# Rephone_core_2G-AtmelSAMD21_v1_0.net
KiCad netlist of a schematic drawn in EAGLE
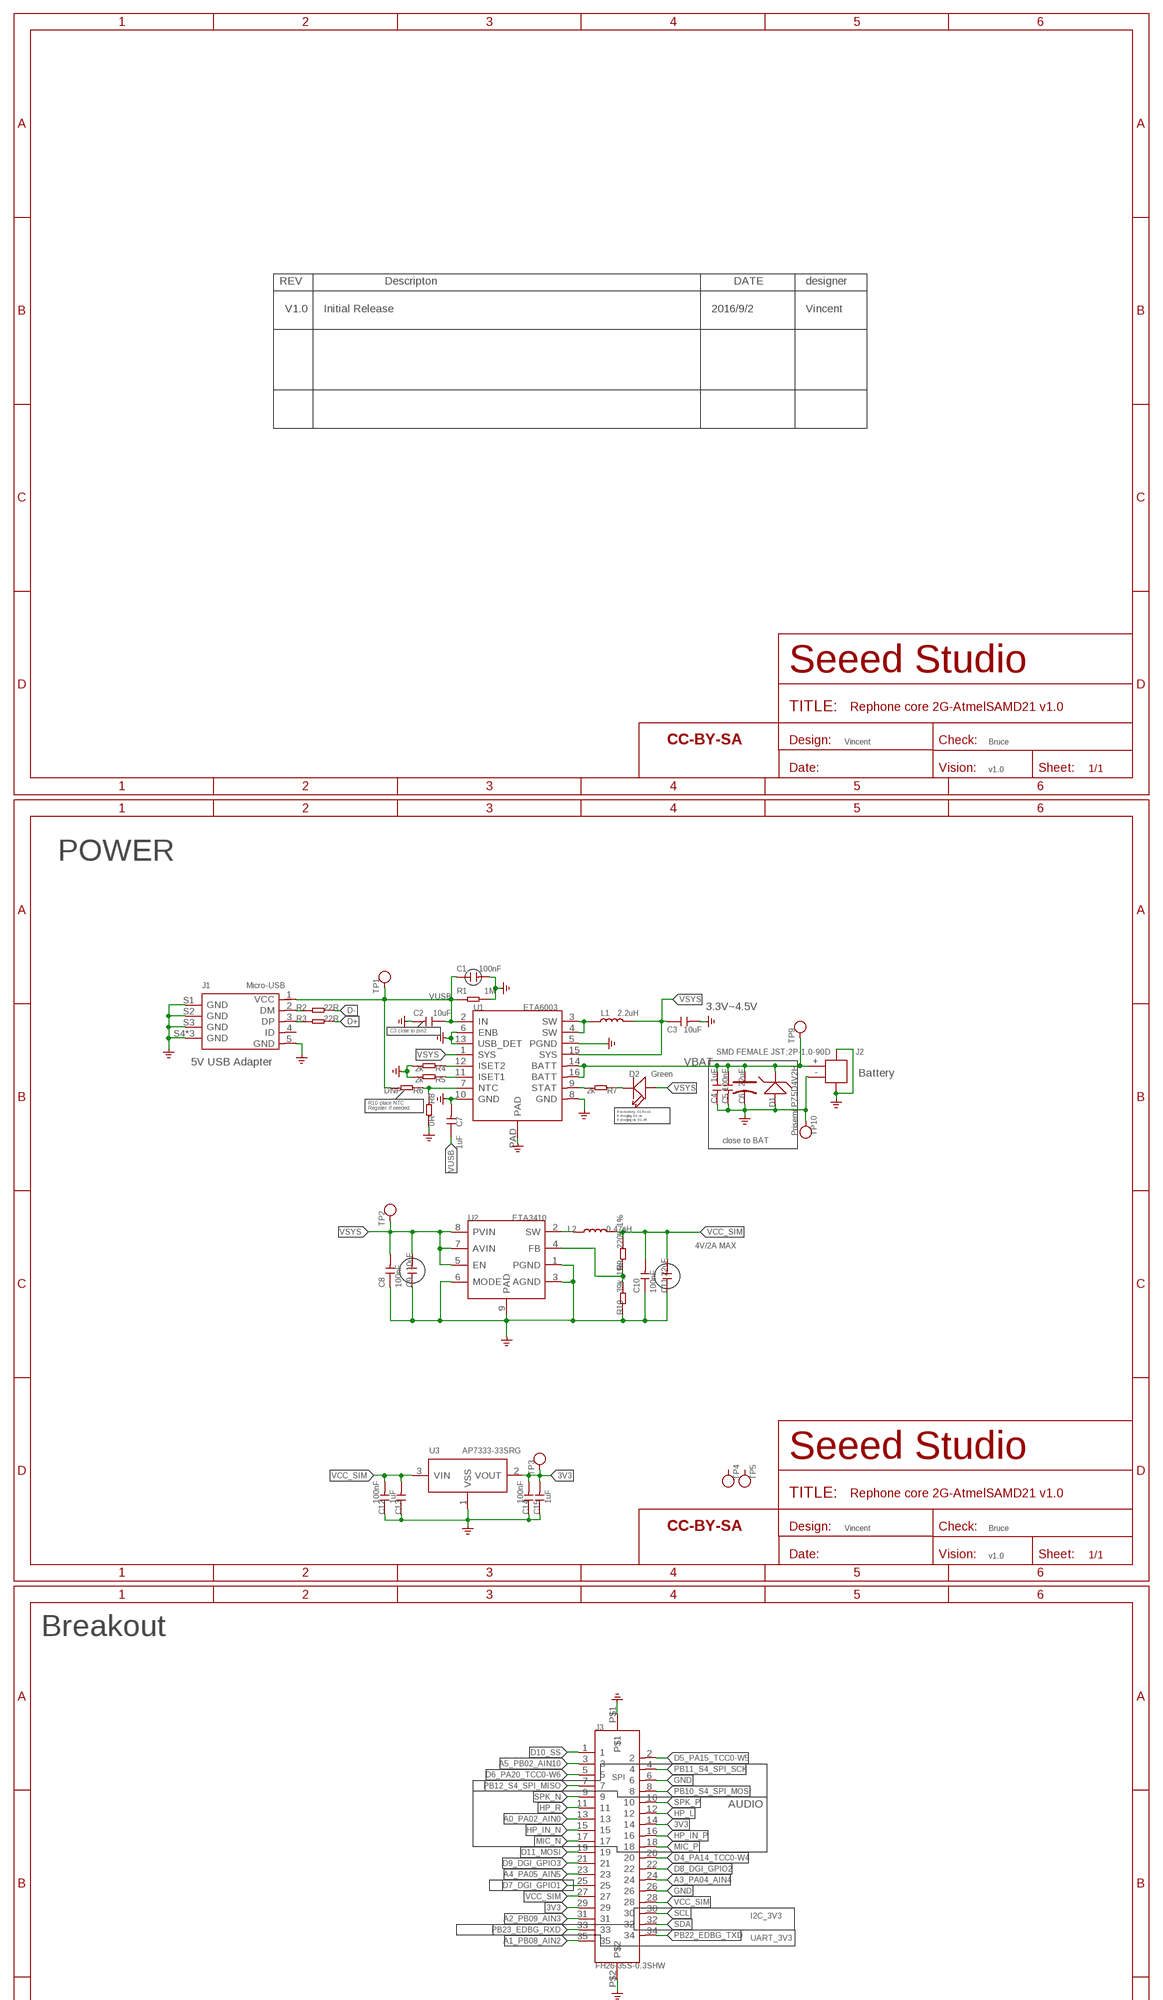
[diagram p0: schematic, sheet 1, part 1 of 2]
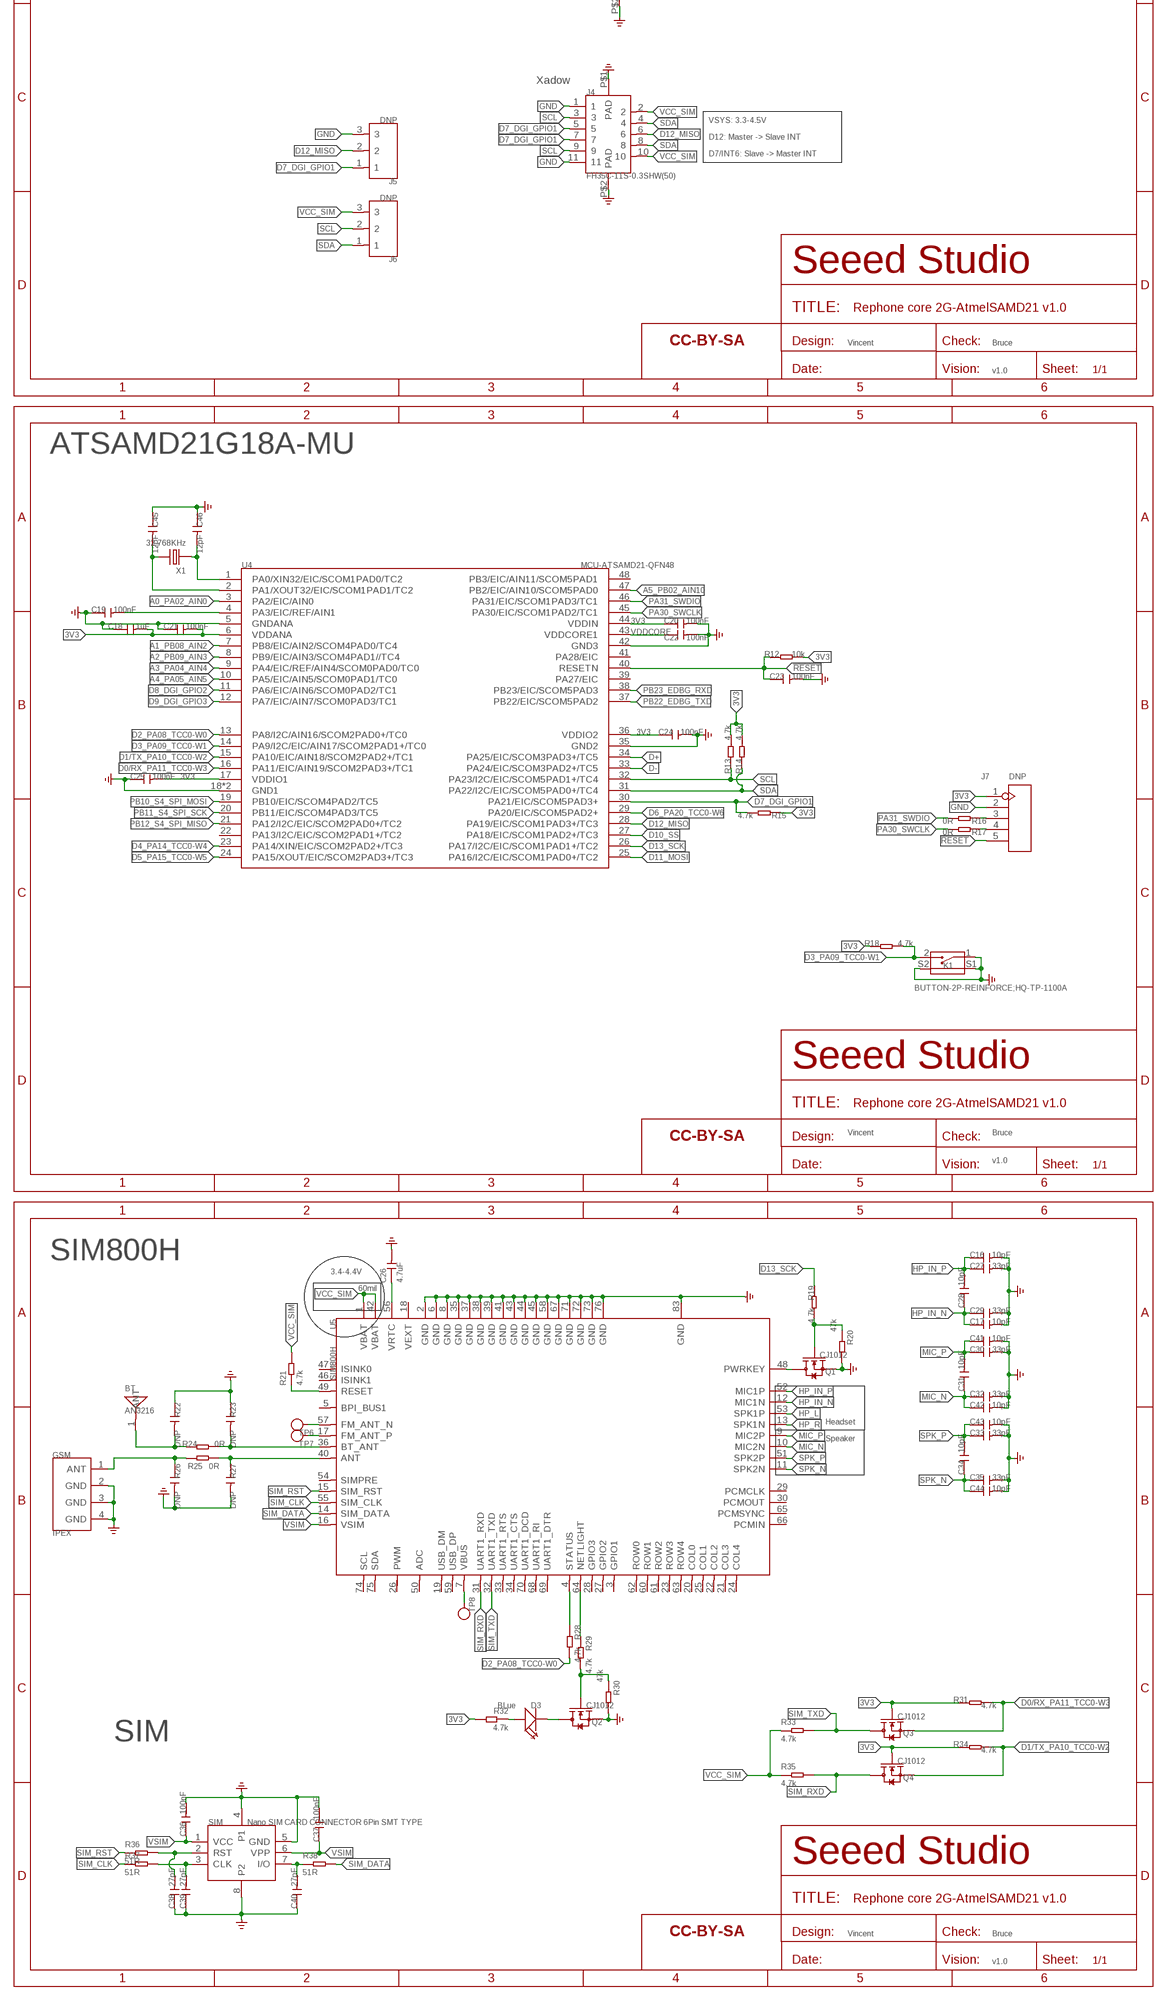
[diagram p1: schematic, sheet 1, part 2 of 2]

(export (version "E")
  (design (tool "Eeschema 10.0.6"))
  (components
    (comp (ref "BT")
      (value "AN3216")
      (footprint "eagle-import:ANT-SMD2P-3.2X1.6X1.04MM")
      (libsource (lib "eagle-import") (part "ANTENNA-AN3216"))
    )
    (comp (ref "C1")
      (value "100nF")
      (footprint "eagle-import:C0201")
      (libsource (lib "eagle-import") (part "CAP-0201"))
    )
    (comp (ref "C2")
      (value "10uF")
      (footprint "eagle-import:C0603")
      (libsource (lib "eagle-import") (part "C-0603"))
    )
    (comp (ref "C3")
      (value "10uF")
      (footprint "eagle-import:C0603")
      (libsource (lib "eagle-import") (part "C-0603"))
    )
    (comp (ref "C4")
      (value "1uF")
      (footprint "eagle-import:C0402")
      (libsource (lib "eagle-import") (part "C-0402"))
    )
    (comp (ref "C5")
      (value "100nF")
      (footprint "eagle-import:C0201")
      (libsource (lib "eagle-import") (part "CAP-0201"))
    )
    (comp (ref "C6")
      (value "22uF")
      (footprint "eagle-import:AVX-A")
      (libsource (lib "eagle-import") (part "CAP-POLAR-AVX-A"))
    )
    (comp (ref "C7")
      (value "1uF")
      (footprint "eagle-import:C0402")
      (libsource (lib "eagle-import") (part "C-0402"))
    )
    (comp (ref "C8")
      (value "100nF")
      (footprint "eagle-import:C0201")
      (libsource (lib "eagle-import") (part "CAP-0201"))
    )
    (comp (ref "C9")
      (value "10uF")
      (footprint "eagle-import:C0603")
      (libsource (lib "eagle-import") (part "C-0603"))
    )
    (comp (ref "C10")
      (value "100nF")
      (footprint "eagle-import:C0201")
      (libsource (lib "eagle-import") (part "CAP-0201"))
    )
    (comp (ref "C11")
      (value "22uF")
      (footprint "eagle-import:C0603")
      (libsource (lib "eagle-import") (part "C-0603"))
    )
    (comp (ref "C12")
      (value "100nF")
      (footprint "eagle-import:C0201")
      (libsource (lib "eagle-import") (part "CAP-0201"))
    )
    (comp (ref "C13")
      (value "1uF")
      (footprint "eagle-import:C0402")
      (libsource (lib "eagle-import") (part "C-0402"))
    )
    (comp (ref "C14")
      (value "100nF")
      (footprint "eagle-import:C0201")
      (libsource (lib "eagle-import") (part "CAP-0201"))
    )
    (comp (ref "C15")
      (value "1uF")
      (footprint "eagle-import:C0402")
      (libsource (lib "eagle-import") (part "C-0402"))
    )
    (comp (ref "C16")
      (value "10pF")
      (footprint "eagle-import:C0201")
      (libsource (lib "eagle-import") (part "CAP-0201"))
    )
    (comp (ref "C17")
      (value "10pF")
      (footprint "eagle-import:C0201")
      (libsource (lib "eagle-import") (part "CAP-0201"))
    )
    (comp (ref "C18")
      (value "1uF")
      (footprint "eagle-import:C0402")
      (libsource (lib "eagle-import") (part "C-0402"))
    )
    (comp (ref "C19")
      (value "100nF")
      (footprint "eagle-import:C0201")
      (libsource (lib "eagle-import") (part "CAP-0201"))
    )
    (comp (ref "C20")
      (value "100nF")
      (footprint "eagle-import:C0201")
      (libsource (lib "eagle-import") (part "CAP-0201"))
    )
    (comp (ref "C21")
      (value "100nF")
      (footprint "eagle-import:C0201")
      (libsource (lib "eagle-import") (part "CAP-0201"))
    )
    (comp (ref "C22")
      (value "100nF")
      (footprint "eagle-import:C0201")
      (libsource (lib "eagle-import") (part "CAP-0201"))
    )
    (comp (ref "C23")
      (value "100nF")
      (footprint "eagle-import:C0201")
      (libsource (lib "eagle-import") (part "CAP-0201"))
    )
    (comp (ref "C24")
      (value "100nF")
      (footprint "eagle-import:C0201")
      (libsource (lib "eagle-import") (part "CAP-0201"))
    )
    (comp (ref "C25")
      (value "100nF")
      (footprint "eagle-import:C0201")
      (libsource (lib "eagle-import") (part "CAP-0201"))
    )
    (comp (ref "C26")
      (value "4.7uF")
      (footprint "eagle-import:C0603")
      (libsource (lib "eagle-import") (part "CAP-0603"))
    )
    (comp (ref "C27")
      (value "33pF")
      (footprint "eagle-import:C0201")
      (libsource (lib "eagle-import") (part "CAP-0201"))
    )
    (comp (ref "C28")
      (value "10pF")
      (footprint "eagle-import:C0201")
      (libsource (lib "eagle-import") (part "CAP-0201"))
    )
    (comp (ref "C29")
      (value "33pF")
      (footprint "eagle-import:C0201")
      (libsource (lib "eagle-import") (part "CAP-0201"))
    )
    (comp (ref "C30")
      (value "33pF")
      (footprint "eagle-import:C0201")
      (libsource (lib "eagle-import") (part "CAP-0201"))
    )
    (comp (ref "C31")
      (value "10pF")
      (footprint "eagle-import:C0201")
      (libsource (lib "eagle-import") (part "CAP-0201"))
    )
    (comp (ref "C32")
      (value "33pF")
      (footprint "eagle-import:C0201")
      (libsource (lib "eagle-import") (part "CAP-0201"))
    )
    (comp (ref "C33")
      (value "33pF")
      (footprint "eagle-import:C0201")
      (libsource (lib "eagle-import") (part "CAP-0201"))
    )
    (comp (ref "C34")
      (value "10pF")
      (footprint "eagle-import:C0201")
      (libsource (lib "eagle-import") (part "CAP-0201"))
    )
    (comp (ref "C35")
      (value "33pF")
      (footprint "eagle-import:C0201")
      (libsource (lib "eagle-import") (part "CAP-0201"))
    )
    (comp (ref "C36")
      (value "100nF")
      (footprint "eagle-import:C0201")
      (libsource (lib "eagle-import") (part "CAP-0201"))
    )
    (comp (ref "C37")
      (value "100nF")
      (footprint "eagle-import:C0201")
      (libsource (lib "eagle-import") (part "CAP-0201"))
    )
    (comp (ref "C38")
      (value "27pF")
      (footprint "eagle-import:C0201")
      (libsource (lib "eagle-import") (part "CAP-0201"))
    )
    (comp (ref "C39")
      (value "27pF")
      (footprint "eagle-import:C0201")
      (libsource (lib "eagle-import") (part "CAP-0201"))
    )
    (comp (ref "C40")
      (value "27pF")
      (footprint "eagle-import:C0201")
      (libsource (lib "eagle-import") (part "CAP-0201"))
    )
    (comp (ref "C41")
      (value "10pF")
      (footprint "eagle-import:C0201")
      (libsource (lib "eagle-import") (part "CAP-0201"))
    )
    (comp (ref "C42")
      (value "10pF")
      (footprint "eagle-import:C0201")
      (libsource (lib "eagle-import") (part "CAP-0201"))
    )
    (comp (ref "C43")
      (value "10pF")
      (footprint "eagle-import:C0201")
      (libsource (lib "eagle-import") (part "CAP-0201"))
    )
    (comp (ref "C44")
      (value "10pF")
      (footprint "eagle-import:C0201")
      (libsource (lib "eagle-import") (part "CAP-0201"))
    )
    (comp (ref "C45")
      (value "12pF")
      (footprint "eagle-import:C0201")
      (libsource (lib "eagle-import") (part "CAP-0201"))
    )
    (comp (ref "C46")
      (value "12pF")
      (footprint "eagle-import:C0201")
      (libsource (lib "eagle-import") (part "CAP-0201"))
    )
    (comp (ref "D1")
      (value "Prisemi;PZ5D4V2H")
      (footprint "eagle-import:SOD-523")
      (libsource (lib "eagle-import") (part "D-ZENER-2P'BZX584CX'"))
    )
    (comp (ref "D2")
      (value "Green")
      (footprint "eagle-import:LED-0402")
      (libsource (lib "eagle-import") (part "LED-0402"))
    )
    (comp (ref "D3")
      (value "BLue")
      (footprint "eagle-import:LED-0402")
      (libsource (lib "eagle-import") (part "LED-0402"))
    )
    (comp (ref "FR1")
      (value "SEEEDSTUDIO-OPEN-SCH-FRAME")
      (footprint "eagle-import:SEEEDSTUDIO-PCB-FRAME")
      (libsource (lib "eagle-import") (part "SEEEDSTUDIO-OPEN-SCH-FRAME"))
    )
    (comp (ref "FR2")
      (value "SEEEDSTUDIO-OPEN-SCH-FRAME")
      (footprint "eagle-import:SEEEDSTUDIO-PCB-FRAME")
      (libsource (lib "eagle-import") (part "SEEEDSTUDIO-OPEN-SCH-FRAME"))
    )
    (comp (ref "FR3")
      (value "SEEEDSTUDIO-OPEN-SCH-FRAME")
      (footprint "eagle-import:SEEEDSTUDIO-PCB-FRAME")
      (libsource (lib "eagle-import") (part "SEEEDSTUDIO-OPEN-SCH-FRAME"))
    )
    (comp (ref "FR4")
      (value "SEEEDSTUDIO-OPEN-SCH-FRAME")
      (footprint "eagle-import:SEEEDSTUDIO-PCB-FRAME")
      (libsource (lib "eagle-import") (part "SEEEDSTUDIO-OPEN-SCH-FRAME"))
    )
    (comp (ref "FR5")
      (value "SEEEDSTUDIO-OPEN-SCH-FRAME")
      (footprint "eagle-import:SEEEDSTUDIO-PCB-FRAME")
      (libsource (lib "eagle-import") (part "SEEEDSTUDIO-OPEN-SCH-FRAME"))
    )
    (comp (ref "GSM")
      (value "IPEX")
      (footprint "eagle-import:ANT-IPEX4-1.7X1.7MM")
      (libsource (lib "eagle-import") (part "ANT_IPEX"))
    )
    (comp (ref "J1")
      (value "Micro-USB")
      (footprint "eagle-import:MICRO-USB5+4P-SMD-0.65-B")
      (libsource (lib "eagle-import") (part "MICRO-USB5+4P5+4P"))
    )
    (comp (ref "J2")
      (value "SMD FEMALE JST;2P-1.0-90D")
      (footprint "eagle-import:HW2-SMD-1.0-90D")
      (libsource (lib "eagle-import") (part "JST-2P-SMD'1.0'"))
    )
    (comp (ref "J3")
      (value "FH26-35S-0.3SHW")
      (footprint "eagle-import:FPC35-SMD-0.3(FH26W)")
      (libsource (lib "eagle-import") (part "FPC-CONNECTER-35P(FH26W-35S-0.3SHW(10))"))
    )
    (comp (ref "J4")
      (value "FH35C-11S-0.3SHW(50)")
      (footprint "eagle-import:FPC11-SMD-0.3(FH35C)")
      (libsource (lib "eagle-import") (part "FPC-CONNECTER-11P(FH35C-11S-0.3SHW(50))"))
    )
    (comp (ref "J5")
      (value "DNP")
      (footprint "eagle-import:3P-DIP-2")
      (libsource (lib "eagle-import") (part "HEADER3"))
    )
    (comp (ref "J6")
      (value "DNP")
      (footprint "eagle-import:3P-DIP-2")
      (libsource (lib "eagle-import") (part "HEADER3"))
    )
    (comp (ref "J7")
      (value "DNP")
      (footprint "eagle-import:H5-SMD-2.0-TEST")
      (libsource (lib "eagle-import") (part "HEADER-5P-TEST"))
    )
    (comp (ref "K1")
      (value "BUTTON-2P-REINFORCE;HQ-TP-1100A")
      (footprint "eagle-import:SW4-SMD-4.5X3.8X1.8MM-90D")
      (libsource (lib "eagle-import") (part "BUTTON-2+2P'HQ-TP-1100A'"))
    )
    (comp (ref "L1")
      (value "2.2uH")
      (footprint "eagle-import:L0805")
      (libsource (lib "eagle-import") (part "INDUCTOR/FERRITE-BEAD'0805'"))
    )
    (comp (ref "L2")
      (value "0.47uH")
      (footprint "eagle-import:L201610")
      (libsource (lib "eagle-import") (part "L-MPM201610SR33_T"))
    )
    (comp (ref "Q1")
      (value "CJ1012")
      (footprint "eagle-import:SOT-523")
      (libsource (lib "eagle-import") (part "MOSFET-N"))
    )
    (comp (ref "Q2")
      (value "CJ1012")
      (footprint "eagle-import:SOT-523")
      (libsource (lib "eagle-import") (part "MOSFET-N"))
    )
    (comp (ref "Q3")
      (value "CJ1012")
      (footprint "eagle-import:SOT-523")
      (libsource (lib "eagle-import") (part "MOSFET-N"))
    )
    (comp (ref "Q4")
      (value "CJ1012")
      (footprint "eagle-import:SOT-523")
      (libsource (lib "eagle-import") (part "MOSFET-N"))
    )
    (comp (ref "R1")
      (value "1M")
      (footprint "eagle-import:R0201")
      (libsource (lib "eagle-import") (part "RES-0201"))
    )
    (comp (ref "R2")
      (value "22R")
      (footprint "eagle-import:R0201")
      (libsource (lib "eagle-import") (part "RES-0201"))
    )
    (comp (ref "R3")
      (value "22R")
      (footprint "eagle-import:R0201")
      (libsource (lib "eagle-import") (part "RES-0201"))
    )
    (comp (ref "R4")
      (value "2k")
      (footprint "eagle-import:R0201")
      (libsource (lib "eagle-import") (part "RES-0201"))
    )
    (comp (ref "R5")
      (value "2k")
      (footprint "eagle-import:R0201")
      (libsource (lib "eagle-import") (part "RES-0201"))
    )
    (comp (ref "R6")
      (value "DNP")
      (footprint "eagle-import:R0201")
      (libsource (lib "eagle-import") (part "RES-0201"))
    )
    (comp (ref "R7")
      (value "2k")
      (footprint "eagle-import:R0201")
      (libsource (lib "eagle-import") (part "RES-0201"))
    )
    (comp (ref "R8")
      (value "0R")
      (footprint "eagle-import:R0201")
      (libsource (lib "eagle-import") (part "RES-0201"))
    )
    (comp (ref "R9")
      (value "220k_1%")
      (footprint "eagle-import:R0201")
      (libsource (lib "eagle-import") (part "RES-0201"))
    )
    (comp (ref "R10")
      (value "39k_1%")
      (footprint "eagle-import:R0201")
      (libsource (lib "eagle-import") (part "RES-0201"))
    )
    (comp (ref "R12")
      (value "10k")
      (footprint "eagle-import:R0201")
      (libsource (lib "eagle-import") (part "RES-0201"))
    )
    (comp (ref "R13")
      (value "4.7k")
      (footprint "eagle-import:R0201")
      (libsource (lib "eagle-import") (part "RES-0201"))
    )
    (comp (ref "R14")
      (value "4.7k")
      (footprint "eagle-import:R0201")
      (libsource (lib "eagle-import") (part "RES-0201"))
    )
    (comp (ref "R15")
      (value "4.7k")
      (footprint "eagle-import:R0201")
      (libsource (lib "eagle-import") (part "RES-0201"))
    )
    (comp (ref "R16")
      (value "0R")
      (footprint "eagle-import:R0201")
      (libsource (lib "eagle-import") (part "RES-0201"))
    )
    (comp (ref "R17")
      (value "0R")
      (footprint "eagle-import:R0201")
      (libsource (lib "eagle-import") (part "RES-0201"))
    )
    (comp (ref "R18")
      (value "4.7k")
      (footprint "eagle-import:R0201")
      (libsource (lib "eagle-import") (part "RES-0201"))
    )
    (comp (ref "R19")
      (value "4.7k")
      (footprint "eagle-import:R0201")
      (libsource (lib "eagle-import") (part "RES-0201"))
    )
    (comp (ref "R20")
      (value "47k")
      (footprint "eagle-import:R0201")
      (libsource (lib "eagle-import") (part "RES-0201"))
    )
    (comp (ref "R21")
      (value "4.7k")
      (footprint "eagle-import:R0201")
      (libsource (lib "eagle-import") (part "RES-0201"))
    )
    (comp (ref "R22")
      (value "DNP")
      (footprint "eagle-import:C0201")
      (libsource (lib "eagle-import") (part "CAP-0201"))
    )
    (comp (ref "R23")
      (value "DNP")
      (footprint "eagle-import:C0201")
      (libsource (lib "eagle-import") (part "CAP-0201"))
    )
    (comp (ref "R24")
      (value "0R")
      (footprint "eagle-import:R0201")
      (libsource (lib "eagle-import") (part "RES-0201"))
    )
    (comp (ref "R25")
      (value "0R")
      (footprint "eagle-import:R0201")
      (libsource (lib "eagle-import") (part "RES-0201"))
    )
    (comp (ref "R26")
      (value "DNP")
      (footprint "eagle-import:C0201")
      (libsource (lib "eagle-import") (part "CAP-0201"))
    )
    (comp (ref "R27")
      (value "DNP")
      (footprint "eagle-import:C0201")
      (libsource (lib "eagle-import") (part "CAP-0201"))
    )
    (comp (ref "R28")
      (value "4.7k")
      (footprint "eagle-import:R0201")
      (libsource (lib "eagle-import") (part "RES-0201"))
    )
    (comp (ref "R29")
      (value "4.7k")
      (footprint "eagle-import:R0201")
      (libsource (lib "eagle-import") (part "RES-0201"))
    )
    (comp (ref "R30")
      (value "47k")
      (footprint "eagle-import:R0201")
      (libsource (lib "eagle-import") (part "RES-0201"))
    )
    (comp (ref "R31")
      (value "4.7k")
      (footprint "eagle-import:R0201")
      (libsource (lib "eagle-import") (part "RES-0201"))
    )
    (comp (ref "R32")
      (value "4.7k")
      (footprint "eagle-import:R0201")
      (libsource (lib "eagle-import") (part "RES-0201"))
    )
    (comp (ref "R33")
      (value "4.7k")
      (footprint "eagle-import:R0201")
      (libsource (lib "eagle-import") (part "RES-0201"))
    )
    (comp (ref "R34")
      (value "4.7k")
      (footprint "eagle-import:R0201")
      (libsource (lib "eagle-import") (part "RES-0201"))
    )
    (comp (ref "R35")
      (value "4.7k")
      (footprint "eagle-import:R0201")
      (libsource (lib "eagle-import") (part "RES-0201"))
    )
    (comp (ref "R36")
      (value "51R")
      (footprint "eagle-import:R0201")
      (libsource (lib "eagle-import") (part "RES-0201"))
    )
    (comp (ref "R37")
      (value "51R")
      (footprint "eagle-import:R0201")
      (libsource (lib "eagle-import") (part "RES-0201"))
    )
    (comp (ref "R38")
      (value "51R")
      (footprint "eagle-import:R0201")
      (libsource (lib "eagle-import") (part "RES-0201"))
    )
    (comp (ref "SIM")
      (value "Nano SIM CARD CONNECTOR 6Pin SMT TYPE")
      (footprint "eagle-import:NANO-SIM6+2P-SMD-12.3X10X1.5MM")
      (libsource (lib "eagle-import") (part "NANO-SIM-6+2P-SMD"))
    )
    (comp (ref "TP1")
      (value "TEST-POINT-23")
      (footprint "eagle-import:TP-D23MIL")
      (libsource (lib "eagle-import") (part "TEST-POINT-23"))
    )
    (comp (ref "TP2")
      (value "TEST-POINT-23")
      (footprint "eagle-import:TP-D23MIL")
      (libsource (lib "eagle-import") (part "TEST-POINT-23"))
    )
    (comp (ref "TP3")
      (value "TEST-POINT-23")
      (footprint "eagle-import:TP-D23MIL")
      (libsource (lib "eagle-import") (part "TEST-POINT-23"))
    )
    (comp (ref "TP4")
      (value "TEST-POINT-23")
      (footprint "eagle-import:TP-D23MIL")
      (libsource (lib "eagle-import") (part "TEST-POINT-23"))
    )
    (comp (ref "TP5")
      (value "TEST-POINT-23")
      (footprint "eagle-import:TP-D23MIL")
      (libsource (lib "eagle-import") (part "TEST-POINT-23"))
    )
    (comp (ref "TP6")
      (value "TEST-POINT'4545'")
      (footprint "eagle-import:TP-D45MIL")
      (fields (field (name "PARTNO") "DNP"))
      (libsource (lib "eagle-import") (part "TEST-POINT'4545'"))
    )
    (comp (ref "TP7")
      (value "TEST-POINT'4545'")
      (footprint "eagle-import:TP-D45MIL")
      (fields (field (name "PARTNO") "DNP"))
      (libsource (lib "eagle-import") (part "TEST-POINT'4545'"))
    )
    (comp (ref "TP8")
      (value "TEST-POINT-23")
      (footprint "eagle-import:TP-D23MIL")
      (libsource (lib "eagle-import") (part "TEST-POINT-23"))
    )
    (comp (ref "TP9")
      (value "TEST-POINT-23")
      (footprint "eagle-import:TP-D23MIL")
      (libsource (lib "eagle-import") (part "TEST-POINT-23"))
    )
    (comp (ref "TP10")
      (value "TEST-POINT-23")
      (footprint "eagle-import:TP-D23MIL")
      (libsource (lib "eagle-import") (part "TEST-POINT-23"))
    )
    (comp (ref "U1")
      (value "ETA6003")
      (footprint "eagle-import:QFN16GA-0.5-3X3MM")
      (libsource (lib "eagle-import") (part "PMIC-ETA6003"))
    )
    (comp (ref "U2")
      (value "ETA3410")
      (footprint "eagle-import:DFN8G-0.5-2X2MM")
      (libsource (lib "eagle-import") (part "CONVERTER-ETA3410"))
    )
    (comp (ref "U3")
      (value "AP7333-33SRG")
      (footprint "eagle-import:SOT-23")
      (libsource (lib "eagle-import") (part "PMIC-XC6206PMR"))
    )
    (comp (ref "U4")
      (value "MCU-ATSAMD21-QFN48")
      (footprint "eagle-import:QFN48-7X7")
      (libsource (lib "eagle-import") (part "MCU-ATSAMD21-QFN48"))
    )
    (comp (ref "U5")
      (value "SIM800H")
      (footprint "eagle-import:GPRS88-SMD-1.4-17.8X45.8X2.4MM")
      (libsource (lib "eagle-import") (part "MOUDLE-GPRS-SIM800H"))
    )
    (comp (ref "X1")
      (value "32.768KHz")
      (footprint "eagle-import:X2-SMD-L2.0X1.2X0.55MM")
      (libsource (lib "eagle-import") (part "CRYSTAL-2P'NX2012SA'"))
    )
  )
  (nets
    (net (code "1") (name "/VBAT") (class "Default")
      (node (ref "C4") (pin "1") (pinfunction "1_1") (pintype "passive"))
      (node (ref "C5") (pin "1") (pinfunction "1_1") (pintype "passive"))
      (node (ref "C6") (pin "+") (pinfunction "+_+") (pintype "passive"))
      (node (ref "D1") (pin "-") (pinfunction "-_-") (pintype "bidirectional"))
      (node (ref "J2") (pin "+") (pinfunction "1_+") (pintype "bidirectional"))
      (node (ref "TP9") (pin "T") (pinfunction "T_T") (pintype "bidirectional"))
      (node (ref "U1") (pin "14") (pinfunction "BATT_14") (pintype "bidirectional"))
      (node (ref "U1") (pin "16") (pinfunction "BATT_16") (pintype "bidirectional"))
    )
    (net (code "2") (name "/VDDCORE") (class "Default")
      (node (ref "C22") (pin "1") (pinfunction "1_1") (pintype "passive"))
      (node (ref "U4") (pin "43") (pinfunction "VDDCORE1_43") (pintype "input"))
    )
    (net (code "3") (name "/~{RESET}") (class "Default")
      (node (ref "C23") (pin "1") (pinfunction "1_1") (pintype "passive"))
      (node (ref "J7") (pin "5") (pinfunction "5_5") (pintype "bidirectional"))
      (node (ref "R12") (pin "2") (pinfunction "2_2") (pintype "passive"))
      (node (ref "U4") (pin "40") (pinfunction "RESETN_40") (pintype "bidirectional"))
    )
    (net (code "4") (name "3V3") (class "Default")
      (node (ref "C14") (pin "2") (pinfunction "2_2") (pintype "passive"))
      (node (ref "C15") (pin "2") (pinfunction "2_2") (pintype "passive"))
      (node (ref "C18") (pin "2") (pinfunction "2_2") (pintype "passive"))
      (node (ref "C20") (pin "1") (pinfunction "1_1") (pintype "passive"))
      (node (ref "C21") (pin "2") (pinfunction "2_2") (pintype "passive"))
      (node (ref "C24") (pin "1") (pinfunction "1_1") (pintype "passive"))
      (node (ref "C25") (pin "2") (pinfunction "2_2") (pintype "passive"))
      (node (ref "J3") (pin "14") (pinfunction "14_14") (pintype "bidirectional"))
      (node (ref "J3") (pin "29") (pinfunction "29_29") (pintype "bidirectional"))
      (node (ref "J7") (pin "1") (pinfunction "1_1") (pintype "bidirectional"))
      (node (ref "Q3") (pin "1") (pinfunction "G_1") (pintype "passive"))
      (node (ref "Q4") (pin "1") (pinfunction "G_1") (pintype "passive"))
      (node (ref "R12") (pin "1") (pinfunction "1_1") (pintype "passive"))
      (node (ref "R13") (pin "2") (pinfunction "2_2") (pintype "passive"))
      (node (ref "R14") (pin "2") (pinfunction "2_2") (pintype "passive"))
      (node (ref "R15") (pin "1") (pinfunction "1_1") (pintype "passive"))
      (node (ref "R18") (pin "1") (pinfunction "1_1") (pintype "passive"))
      (node (ref "R31") (pin "1") (pinfunction "1_1") (pintype "passive"))
      (node (ref "R32") (pin "2") (pinfunction "2_2") (pintype "passive"))
      (node (ref "R34") (pin "1") (pinfunction "1_1") (pintype "passive"))
      (node (ref "TP3") (pin "T") (pinfunction "T_T") (pintype "bidirectional"))
      (node (ref "U3") (pin "2") (pinfunction "VOUT_2") (pintype "bidirectional"))
      (node (ref "U4") (pin "17") (pinfunction "VDDIO1_17") (pintype "power_in"))
      (node (ref "U4") (pin "36") (pinfunction "VDDIO2_36") (pintype "power_in"))
      (node (ref "U4") (pin "44") (pinfunction "VDDIN_44") (pintype "power_in"))
      (node (ref "U4") (pin "6") (pinfunction "VDDANA_6") (pintype "power_in"))
    )
    (net (code "5") (name "A0_PA02_AIN0") (class "Default")
      (node (ref "J3") (pin "13") (pinfunction "13_13") (pintype "bidirectional"))
      (node (ref "U4") (pin "3") (pinfunction "PA2/EIC/AIN0_3") (pintype "bidirectional"))
    )
    (net (code "6") (name "A1_PB08_AIN2") (class "Default")
      (node (ref "J3") (pin "35") (pinfunction "35_35") (pintype "bidirectional"))
      (node (ref "U4") (pin "7") (pinfunction "PB8/EIC/AIN2/SCOM4PAD0/TC4_7") (pintype "bidirectional"))
    )
    (net (code "7") (name "A2_PB09_AIN3") (class "Default")
      (node (ref "J3") (pin "31") (pinfunction "31_31") (pintype "bidirectional"))
      (node (ref "U4") (pin "8") (pinfunction "PB9/EIC/AIN3/SCOM4PAD1//TC4_8") (pintype "bidirectional"))
    )
    (net (code "8") (name "A3_PA04_AIN4") (class "Default")
      (node (ref "J3") (pin "24") (pinfunction "24_24") (pintype "bidirectional"))
      (node (ref "U4") (pin "9") (pinfunction "PA4/EIC/REF/AIN4/SCOM0PAD0/TC0_9") (pintype "bidirectional"))
    )
    (net (code "9") (name "A4_PA05_AIN5") (class "Default")
      (node (ref "J3") (pin "23") (pinfunction "23_23") (pintype "bidirectional"))
      (node (ref "U4") (pin "10") (pinfunction "PA5/EIC/AIN5/SCOM0PAD1/TC0_10") (pintype "bidirectional"))
    )
    (net (code "10") (name "A5_PB02_AIN10") (class "Default")
      (node (ref "J3") (pin "3") (pinfunction "3_3") (pintype "bidirectional"))
      (node (ref "U4") (pin "47") (pinfunction "PB2/EIC/AIN10/SCOM5PAD0_47") (pintype "bidirectional"))
    )
    (net (code "11") (name "D+") (class "Default")
      (node (ref "R3") (pin "2") (pinfunction "2_2") (pintype "passive"))
      (node (ref "U4") (pin "34") (pinfunction "PA25/EIC/SCOM3PAD3+/TC5_34") (pintype "bidirectional"))
    )
    (net (code "12") (name "D-") (class "Default")
      (node (ref "R2") (pin "2") (pinfunction "2_2") (pintype "passive"))
      (node (ref "U4") (pin "33") (pinfunction "PA24/EIC/SCOM3PAD2+/TC5_33") (pintype "bidirectional"))
    )
    (net (code "13") (name "D0{slash}RX_PA11_TCC0-W3") (class "Default")
      (node (ref "Q3") (pin "2") (pinfunction "S_2") (pintype "passive"))
      (node (ref "R31") (pin "2") (pinfunction "2_2") (pintype "passive"))
      (node (ref "U4") (pin "16") (pinfunction "PA11/EIC/AIN19/SCOM2PAD3+/TC1_16") (pintype "bidirectional"))
    )
    (net (code "14") (name "D1{slash}TX_PA10_TCC0-W2") (class "Default")
      (node (ref "Q4") (pin "2") (pinfunction "S_2") (pintype "passive"))
      (node (ref "R34") (pin "2") (pinfunction "2_2") (pintype "passive"))
      (node (ref "U4") (pin "15") (pinfunction "PA10/EIC/AIN18/SCOM2PAD2+/TC1_15") (pintype "bidirectional"))
    )
    (net (code "15") (name "D2_PA08_TCC0-W0") (class "Default")
      (node (ref "R28") (pin "2") (pinfunction "2_2") (pintype "passive"))
      (node (ref "U4") (pin "13") (pinfunction "PA8/I2C/AIN16/SCOM2PAD0+/TC0_13") (pintype "bidirectional"))
    )
    (net (code "16") (name "D3_PA09_TCC0-W1") (class "Default")
      (node (ref "K1") (pin "2") (pinfunction "2_2") (pintype "bidirectional"))
      (node (ref "R18") (pin "2") (pinfunction "2_2") (pintype "passive"))
      (node (ref "U4") (pin "14") (pinfunction "PA9/I2C/EIC/AIN17/SCOM2PAD1+/TC0_14") (pintype "bidirectional"))
    )
    (net (code "17") (name "D4_PA14_TCC0-W4") (class "Default")
      (node (ref "J3") (pin "20") (pinfunction "20_20") (pintype "bidirectional"))
      (node (ref "U4") (pin "23") (pinfunction "PA14/XIN/EIC/SCOM2PAD2+/TC3_23") (pintype "bidirectional"))
    )
    (net (code "18") (name "D5_PA15_TCC0-W5") (class "Default")
      (node (ref "J3") (pin "2") (pinfunction "2_2") (pintype "bidirectional"))
      (node (ref "U4") (pin "24") (pinfunction "PA15/XOUT/EIC/SCOM2PAD3+/TC3_24") (pintype "bidirectional"))
    )
    (net (code "19") (name "D6_PA20_TCC0-W6") (class "Default")
      (node (ref "J3") (pin "5") (pinfunction "5_5") (pintype "bidirectional"))
      (node (ref "U4") (pin "29") (pinfunction "PA20/EIC/SCOM5PAD2+_29") (pintype "bidirectional"))
    )
    (net (code "20") (name "D7_DGI_GPIO1") (class "Default")
      (node (ref "J3") (pin "25") (pinfunction "25_25") (pintype "bidirectional"))
      (node (ref "J4") (pin "5") (pinfunction "5_5") (pintype "bidirectional"))
      (node (ref "J4") (pin "7") (pinfunction "7_7") (pintype "bidirectional"))
      (node (ref "J5") (pin "1") (pinfunction "1_1") (pintype "bidirectional"))
      (node (ref "R15") (pin "2") (pinfunction "2_2") (pintype "passive"))
      (node (ref "U4") (pin "30") (pinfunction "PA21/EIC/SCOM5PAD3+_30") (pintype "bidirectional"))
    )
    (net (code "21") (name "D8_DGI_GPIO2") (class "Default")
      (node (ref "J3") (pin "22") (pinfunction "22_22") (pintype "bidirectional"))
      (node (ref "U4") (pin "11") (pinfunction "PA6/EIC/AIN6/SCOM0PAD2/TC1_11") (pintype "bidirectional"))
    )
    (net (code "22") (name "D9_DGI_GPIO3") (class "Default")
      (node (ref "J3") (pin "21") (pinfunction "21_21") (pintype "bidirectional"))
      (node (ref "U4") (pin "12") (pinfunction "PA7/EIC/AIN7/SCOM0PAD3/TC1_12") (pintype "bidirectional"))
    )
    (net (code "23") (name "D10_SS") (class "Default")
      (node (ref "J3") (pin "1") (pinfunction "1_1") (pintype "bidirectional"))
      (node (ref "U4") (pin "27") (pinfunction "PA18/EIC/SCOM1PAD2+/TC3_27") (pintype "bidirectional"))
    )
    (net (code "24") (name "D11_MOSI") (class "Default")
      (node (ref "J3") (pin "19") (pinfunction "19_19") (pintype "bidirectional"))
      (node (ref "U4") (pin "25") (pinfunction "PA16/I2C/EIC/SCOM1PAD0+/TC2_25") (pintype "bidirectional"))
    )
    (net (code "25") (name "D12_MISO") (class "Default")
      (node (ref "J4") (pin "6") (pinfunction "6_6") (pintype "bidirectional"))
      (node (ref "J5") (pin "2") (pinfunction "2_2") (pintype "bidirectional"))
      (node (ref "U4") (pin "28") (pinfunction "PA19/EIC/SCOM1PAD3+/TC3_28") (pintype "bidirectional"))
    )
    (net (code "26") (name "D13_SCK") (class "Default")
      (node (ref "R19") (pin "1") (pinfunction "1_1") (pintype "passive"))
      (node (ref "U4") (pin "26") (pinfunction "PA17/I2C/EIC/SCOM1PAD1+/TC2_26") (pintype "bidirectional"))
    )
    (net (code "27") (name "GND") (class "Default")
      (node (ref "C1") (pin "2") (pinfunction "2_2") (pintype "passive"))
      (node (ref "C10") (pin "1") (pinfunction "1_1") (pintype "passive"))
      (node (ref "C11") (pin "1") (pinfunction "1_1") (pintype "passive"))
      (node (ref "C12") (pin "1") (pinfunction "1_1") (pintype "passive"))
      (node (ref "C13") (pin "1") (pinfunction "1_1") (pintype "passive"))
      (node (ref "C14") (pin "1") (pinfunction "1_1") (pintype "passive"))
      (node (ref "C15") (pin "1") (pinfunction "1_1") (pintype "passive"))
      (node (ref "C16") (pin "2") (pinfunction "2_2") (pintype "passive"))
      (node (ref "C17") (pin "2") (pinfunction "2_2") (pintype "passive"))
      (node (ref "C18") (pin "1") (pinfunction "1_1") (pintype "passive"))
      (node (ref "C19") (pin "1") (pinfunction "1_1") (pintype "passive"))
      (node (ref "C2") (pin "2") (pinfunction "2_2") (pintype "passive"))
      (node (ref "C20") (pin "2") (pinfunction "2_2") (pintype "passive"))
      (node (ref "C21") (pin "1") (pinfunction "1_1") (pintype "passive"))
      (node (ref "C22") (pin "2") (pinfunction "2_2") (pintype "passive"))
      (node (ref "C23") (pin "2") (pinfunction "2_2") (pintype "passive"))
      (node (ref "C24") (pin "2") (pinfunction "2_2") (pintype "passive"))
      (node (ref "C25") (pin "1") (pinfunction "1_1") (pintype "passive"))
      (node (ref "C26") (pin "2") (pinfunction "2_2") (pintype "passive"))
      (node (ref "C27") (pin "2") (pinfunction "2_2") (pintype "passive"))
      (node (ref "C29") (pin "2") (pinfunction "2_2") (pintype "passive"))
      (node (ref "C3") (pin "2") (pinfunction "2_2") (pintype "passive"))
      (node (ref "C30") (pin "2") (pinfunction "2_2") (pintype "passive"))
      (node (ref "C32") (pin "2") (pinfunction "2_2") (pintype "passive"))
      (node (ref "C33") (pin "2") (pinfunction "2_2") (pintype "passive"))
      (node (ref "C35") (pin "2") (pinfunction "2_2") (pintype "passive"))
      (node (ref "C36") (pin "2") (pinfunction "2_2") (pintype "passive"))
      (node (ref "C37") (pin "2") (pinfunction "2_2") (pintype "passive"))
      (node (ref "C38") (pin "1") (pinfunction "1_1") (pintype "passive"))
      (node (ref "C39") (pin "1") (pinfunction "1_1") (pintype "passive"))
      (node (ref "C4") (pin "2") (pinfunction "2_2") (pintype "passive"))
      (node (ref "C40") (pin "1") (pinfunction "1_1") (pintype "passive"))
      (node (ref "C41") (pin "2") (pinfunction "2_2") (pintype "passive"))
      (node (ref "C42") (pin "2") (pinfunction "2_2") (pintype "passive"))
      (node (ref "C43") (pin "2") (pinfunction "2_2") (pintype "passive"))
      (node (ref "C44") (pin "2") (pinfunction "2_2") (pintype "passive"))
      (node (ref "C45") (pin "1") (pinfunction "1_1") (pintype "passive"))
      (node (ref "C46") (pin "1") (pinfunction "1_1") (pintype "passive"))
      (node (ref "C5") (pin "2") (pinfunction "2_2") (pintype "passive"))
      (node (ref "C6") (pin "-") (pinfunction "-_-") (pintype "passive"))
      (node (ref "C7") (pin "2") (pinfunction "2_2") (pintype "passive"))
      (node (ref "C8") (pin "1") (pinfunction "1_1") (pintype "passive"))
      (node (ref "C9") (pin "1") (pinfunction "1_1") (pintype "passive"))
      (node (ref "D1") (pin "+") (pinfunction "+_+") (pintype "bidirectional"))
      (node (ref "GSM") (pin "2") (pinfunction "GND_2") (pintype "bidirectional"))
      (node (ref "GSM") (pin "3") (pinfunction "GND_3") (pintype "bidirectional"))
      (node (ref "GSM") (pin "4") (pinfunction "GND_4") (pintype "bidirectional"))
      (node (ref "J1") (pin "5") (pinfunction "GND_5") (pintype "bidirectional"))
      (node (ref "J1") (pin "S1") (pinfunction "GND_S1") (pintype "bidirectional"))
      (node (ref "J1") (pin "S2") (pinfunction "GND_S2") (pintype "bidirectional"))
      (node (ref "J1") (pin "S3") (pinfunction "GND_S3") (pintype "bidirectional"))
      (node (ref "J1") (pin "S4") (pinfunction "GND_S4") (pintype "bidirectional"))
      (node (ref "J1") (pin "S5") (pinfunction "GND_S5") (pintype "bidirectional"))
      (node (ref "J1") (pin "S6") (pinfunction "GND_S6") (pintype "bidirectional"))
      (node (ref "J2") (pin "-") (pinfunction "2_-") (pintype "bidirectional"))
      (node (ref "J2") (pin "3") (pinfunction "3_3") (pintype "bidirectional"))
      (node (ref "J2") (pin "4") (pinfunction "4_4") (pintype "bidirectional"))
      (node (ref "J3") (pin "26") (pinfunction "26_26") (pintype "bidirectional"))
      (node (ref "J3") (pin "6") (pinfunction "6_6") (pintype "bidirectional"))
      (node (ref "J3") (pin "P$1") (pinfunction "P$1_P$1") (pintype "bidirectional"))
      (node (ref "J3") (pin "P$2") (pinfunction "P$2_P$2") (pintype "bidirectional"))
      (node (ref "J4") (pin "1") (pinfunction "1_1") (pintype "bidirectional"))
      (node (ref "J4") (pin "11") (pinfunction "11_11") (pintype "bidirectional"))
      (node (ref "J4") (pin "P$1") (pinfunction "PAD_P$1") (pintype "bidirectional"))
      (node (ref "J4") (pin "P$2") (pinfunction "PAD_P$2") (pintype "bidirectional"))
      (node (ref "J5") (pin "3") (pinfunction "3_3") (pintype "bidirectional"))
      (node (ref "J7") (pin "2") (pinfunction "2_2") (pintype "bidirectional"))
      (node (ref "K1") (pin "1") (pinfunction "1_1") (pintype "bidirectional"))
      (node (ref "K1") (pin "S1") (pinfunction "S1_S1") (pintype "bidirectional"))
      (node (ref "K1") (pin "S2") (pinfunction "S2_S2") (pintype "bidirectional"))
      (node (ref "Q1") (pin "2") (pinfunction "S_2") (pintype "passive"))
      (node (ref "Q2") (pin "2") (pinfunction "S_2") (pintype "passive"))
      (node (ref "R1") (pin "2") (pinfunction "2_2") (pintype "passive"))
      (node (ref "R10") (pin "1") (pinfunction "1_1") (pintype "passive"))
      (node (ref "R20") (pin "2") (pinfunction "2_2") (pintype "passive"))
      (node (ref "R22") (pin "1") (pinfunction "1_1") (pintype "passive"))
      (node (ref "R23") (pin "1") (pinfunction "1_1") (pintype "passive"))
      (node (ref "R26") (pin "2") (pinfunction "2_2") (pintype "passive"))
      (node (ref "R27") (pin "2") (pinfunction "2_2") (pintype "passive"))
      (node (ref "R30") (pin "2") (pinfunction "2_2") (pintype "passive"))
      (node (ref "R4") (pin "2") (pinfunction "2_2") (pintype "passive"))
      (node (ref "R5") (pin "2") (pinfunction "2_2") (pintype "passive"))
      (node (ref "R8") (pin "2") (pinfunction "2_2") (pintype "passive"))
      (node (ref "SIM") (pin "4") (pinfunction "P1_4") (pintype "bidirectional"))
      (node (ref "SIM") (pin "5") (pinfunction "GND_5") (pintype "bidirectional"))
      (node (ref "SIM") (pin "8") (pinfunction "P2_8") (pintype "bidirectional"))
      (node (ref "TP10") (pin "T") (pinfunction "T_T") (pintype "bidirectional"))
      (node (ref "U1") (pin "10") (pinfunction "GND_10") (pintype "bidirectional"))
      (node (ref "U1") (pin "13") (pinfunction "USB_DET_13") (pintype "bidirectional"))
      (node (ref "U1") (pin "5") (pinfunction "PGND_5") (pintype "bidirectional"))
      (node (ref "U1") (pin "6") (pinfunction "ENB_6") (pintype "bidirectional"))
      (node (ref "U1") (pin "8") (pinfunction "GND_8") (pintype "bidirectional"))
      (node (ref "U1") (pin "PAD") (pinfunction "PAD_PAD") (pintype "bidirectional"))
      (node (ref "U2") (pin "1") (pinfunction "PGND_1") (pintype "bidirectional"))
      (node (ref "U2") (pin "3") (pinfunction "AGND_3") (pintype "bidirectional"))
      (node (ref "U2") (pin "6") (pinfunction "MODE_6") (pintype "bidirectional"))
      (node (ref "U2") (pin "9") (pinfunction "PAD_9") (pintype "bidirectional"))
      (node (ref "U3") (pin "1") (pinfunction "VSS_1") (pintype "bidirectional"))
      (node (ref "U4") (pin "18") (pinfunction "GND1_18") (pintype "power_in"))
      (node (ref "U4") (pin "35") (pinfunction "GND2_35") (pintype "power_in"))
      (node (ref "U4") (pin "42") (pinfunction "GND3_42") (pintype "power_in"))
      (node (ref "U4") (pin "5") (pinfunction "GNDANA_5") (pintype "power_in"))
      (node (ref "U4") (pin "PAD") (pinfunction "GND1_PAD") (pintype "power_in"))
      (node (ref "U5") (pin "2") (pinfunction "GND_2") (pintype "bidirectional"))
      (node (ref "U5") (pin "35") (pinfunction "GND_35") (pintype "bidirectional"))
      (node (ref "U5") (pin "37") (pinfunction "GND_37") (pintype "bidirectional"))
      (node (ref "U5") (pin "38") (pinfunction "GND_38") (pintype "bidirectional"))
      (node (ref "U5") (pin "39") (pinfunction "GND_39") (pintype "bidirectional"))
      (node (ref "U5") (pin "41") (pinfunction "GND_41") (pintype "bidirectional"))
      (node (ref "U5") (pin "43") (pinfunction "GND_43") (pintype "bidirectional"))
      (node (ref "U5") (pin "44") (pinfunction "GND_44") (pintype "bidirectional"))
      (node (ref "U5") (pin "45") (pinfunction "GND_45") (pintype "bidirectional"))
      (node (ref "U5") (pin "58") (pinfunction "GND_58") (pintype "bidirectional"))
      (node (ref "U5") (pin "6") (pinfunction "GND_6") (pintype "bidirectional"))
      (node (ref "U5") (pin "67") (pinfunction "GND_67") (pintype "bidirectional"))
      (node (ref "U5") (pin "71") (pinfunction "GND_71") (pintype "bidirectional"))
      (node (ref "U5") (pin "72") (pinfunction "GND_72") (pintype "bidirectional"))
      (node (ref "U5") (pin "73") (pinfunction "GND_73") (pintype "bidirectional"))
      (node (ref "U5") (pin "76") (pinfunction "GND_76") (pintype "bidirectional"))
      (node (ref "U5") (pin "8") (pinfunction "GND_8") (pintype "bidirectional"))
      (node (ref "U5") (pin "83") (pinfunction "GND_83") (pintype "bidirectional"))
    )
    (net (code "28") (name "HP_IN_N") (class "Default")
      (node (ref "C17") (pin "1") (pinfunction "1_1") (pintype "passive"))
      (node (ref "C28") (pin "1") (pinfunction "1_1") (pintype "passive"))
      (node (ref "C29") (pin "1") (pinfunction "1_1") (pintype "passive"))
      (node (ref "J3") (pin "15") (pinfunction "15_15") (pintype "bidirectional"))
      (node (ref "U5") (pin "12") (pinfunction "MIC1N_12") (pintype "bidirectional"))
    )
    (net (code "29") (name "HP_IN_P") (class "Default")
      (node (ref "C16") (pin "1") (pinfunction "1_1") (pintype "passive"))
      (node (ref "C27") (pin "1") (pinfunction "1_1") (pintype "passive"))
      (node (ref "C28") (pin "2") (pinfunction "2_2") (pintype "passive"))
      (node (ref "J3") (pin "16") (pinfunction "16_16") (pintype "bidirectional"))
      (node (ref "U5") (pin "52") (pinfunction "MIC1P_52") (pintype "bidirectional"))
    )
    (net (code "30") (name "HP_L") (class "Default")
      (node (ref "J3") (pin "12") (pinfunction "12_12") (pintype "bidirectional"))
      (node (ref "U5") (pin "53") (pinfunction "SPK1P_53") (pintype "bidirectional"))
    )
    (net (code "31") (name "HP_R") (class "Default")
      (node (ref "J3") (pin "11") (pinfunction "11_11") (pintype "bidirectional"))
      (node (ref "U5") (pin "13") (pinfunction "SPK1N_13") (pintype "bidirectional"))
    )
    (net (code "32") (name "MIC_N") (class "Default")
      (node (ref "C31") (pin "1") (pinfunction "1_1") (pintype "passive"))
      (node (ref "C32") (pin "1") (pinfunction "1_1") (pintype "passive"))
      (node (ref "C42") (pin "1") (pinfunction "1_1") (pintype "passive"))
      (node (ref "J3") (pin "17") (pinfunction "17_17") (pintype "bidirectional"))
      (node (ref "U5") (pin "10") (pinfunction "MIC2N_10") (pintype "bidirectional"))
    )
    (net (code "33") (name "MIC_P") (class "Default")
      (node (ref "C30") (pin "1") (pinfunction "1_1") (pintype "passive"))
      (node (ref "C31") (pin "2") (pinfunction "2_2") (pintype "passive"))
      (node (ref "C41") (pin "1") (pinfunction "1_1") (pintype "passive"))
      (node (ref "J3") (pin "18") (pinfunction "18_18") (pintype "bidirectional"))
      (node (ref "U5") (pin "9") (pinfunction "MIC2P_9") (pintype "bidirectional"))
    )
    (net (code "34") (name "Net-(BT-ANT)") (class "Default")
      (node (ref "BT") (pin "1") (pinfunction "ANT_1") (pintype "bidirectional"))
      (node (ref "R22") (pin "2") (pinfunction "2_2") (pintype "passive"))
      (node (ref "R24") (pin "2") (pinfunction "2_2") (pintype "passive"))
    )
    (net (code "35") (name "Net-(D2-Pad-)") (class "Default")
      (node (ref "D2") (pin "-") (pinfunction "-_-") (pintype "passive"))
      (node (ref "R7") (pin "1") (pinfunction "1_1") (pintype "passive"))
    )
    (net (code "36") (name "Net-(D3-Pad+)") (class "Default")
      (node (ref "D3") (pin "+") (pinfunction "+_+") (pintype "passive"))
      (node (ref "R32") (pin "1") (pinfunction "1_1") (pintype "passive"))
    )
    (net (code "37") (name "Net-(GSM-ANT)") (class "Default")
      (node (ref "GSM") (pin "1") (pinfunction "ANT_1") (pintype "bidirectional"))
      (node (ref "R25") (pin "2") (pinfunction "2_2") (pintype "passive"))
      (node (ref "R26") (pin "1") (pinfunction "1_1") (pintype "passive"))
    )
    (net (code "38") (name "Net-(J1-DM)") (class "Default")
      (node (ref "J1") (pin "2") (pinfunction "DM_2") (pintype "bidirectional"))
      (node (ref "R2") (pin "1") (pinfunction "1_1") (pintype "passive"))
    )
    (net (code "39") (name "Net-(J1-DP)") (class "Default")
      (node (ref "J1") (pin "3") (pinfunction "DP_3") (pintype "bidirectional"))
      (node (ref "R3") (pin "1") (pinfunction "1_1") (pintype "passive"))
    )
    (net (code "40") (name "Net-(J7-Pad3)") (class "Default")
      (node (ref "J7") (pin "3") (pinfunction "3_3") (pintype "bidirectional"))
      (node (ref "R16") (pin "1") (pinfunction "1_1") (pintype "passive"))
    )
    (net (code "41") (name "Net-(J7-Pad4)") (class "Default")
      (node (ref "J7") (pin "4") (pinfunction "4_4") (pintype "bidirectional"))
      (node (ref "R17") (pin "1") (pinfunction "1_1") (pintype "passive"))
    )
    (net (code "42") (name "Net-(L1-Pad1)") (class "Default")
      (node (ref "L1") (pin "1") (pinfunction "1_1") (pintype "passive"))
      (node (ref "U1") (pin "3") (pinfunction "SW_3") (pintype "bidirectional"))
      (node (ref "U1") (pin "4") (pinfunction "SW_4") (pintype "bidirectional"))
    )
    (net (code "43") (name "Net-(Q1-D)") (class "Default")
      (node (ref "Q1") (pin "3") (pinfunction "D_3") (pintype "passive"))
      (node (ref "U5") (pin "48") (pinfunction "PWRKEY_48") (pintype "bidirectional"))
    )
    (net (code "44") (name "Net-(Q1-G)") (class "Default")
      (node (ref "Q1") (pin "1") (pinfunction "G_1") (pintype "passive"))
      (node (ref "R19") (pin "2") (pinfunction "2_2") (pintype "passive"))
      (node (ref "R20") (pin "1") (pinfunction "1_1") (pintype "passive"))
    )
    (net (code "45") (name "Net-(Q2-D)") (class "Default")
      (node (ref "D3") (pin "-") (pinfunction "-_-") (pintype "passive"))
      (node (ref "Q2") (pin "3") (pinfunction "D_3") (pintype "passive"))
    )
    (net (code "46") (name "Net-(Q2-G)") (class "Default")
      (node (ref "Q2") (pin "1") (pinfunction "G_1") (pintype "passive"))
      (node (ref "R29") (pin "2") (pinfunction "2_2") (pintype "passive"))
      (node (ref "R30") (pin "1") (pinfunction "1_1") (pintype "passive"))
    )
    (net (code "47") (name "Net-(SIM-CLK)") (class "Default")
      (node (ref "C39") (pin "2") (pinfunction "2_2") (pintype "passive"))
      (node (ref "R37") (pin "2") (pinfunction "2_2") (pintype "passive"))
      (node (ref "SIM") (pin "3") (pinfunction "CLK_3") (pintype "bidirectional"))
    )
    (net (code "48") (name "Net-(SIM-I{slash}O)") (class "Default")
      (node (ref "C40") (pin "2") (pinfunction "2_2") (pintype "passive"))
      (node (ref "R38") (pin "1") (pinfunction "1_1") (pintype "passive"))
      (node (ref "SIM") (pin "7") (pinfunction "I/O_7") (pintype "bidirectional"))
    )
    (net (code "49") (name "Net-(SIM-RST)") (class "Default")
      (node (ref "C38") (pin "2") (pinfunction "2_2") (pintype "passive"))
      (node (ref "R36") (pin "2") (pinfunction "2_2") (pintype "passive"))
      (node (ref "SIM") (pin "2") (pinfunction "RST_2") (pintype "bidirectional"))
    )
    (net (code "50") (name "Net-(U1-ISET1)") (class "Default")
      (node (ref "R5") (pin "1") (pinfunction "1_1") (pintype "passive"))
      (node (ref "U1") (pin "11") (pinfunction "ISET1_11") (pintype "bidirectional"))
    )
    (net (code "51") (name "Net-(U1-ISET2)") (class "Default")
      (node (ref "R4") (pin "1") (pinfunction "1_1") (pintype "passive"))
      (node (ref "U1") (pin "12") (pinfunction "ISET2_12") (pintype "bidirectional"))
    )
    (net (code "52") (name "Net-(U1-NTC)") (class "Default")
      (node (ref "R6") (pin "1") (pinfunction "1_1") (pintype "passive"))
      (node (ref "R8") (pin "1") (pinfunction "1_1") (pintype "passive"))
      (node (ref "U1") (pin "7") (pinfunction "NTC_7") (pintype "bidirectional"))
    )
    (net (code "53") (name "Net-(U1-STAT)") (class "Default")
      (node (ref "R7") (pin "2") (pinfunction "2_2") (pintype "passive"))
      (node (ref "U1") (pin "9") (pinfunction "STAT_9") (pintype "bidirectional"))
    )
    (net (code "54") (name "Net-(U2-FB)") (class "Default")
      (node (ref "R10") (pin "2") (pinfunction "2_2") (pintype "passive"))
      (node (ref "R9") (pin "1") (pinfunction "1_1") (pintype "passive"))
      (node (ref "U2") (pin "4") (pinfunction "FB_4") (pintype "bidirectional"))
    )
    (net (code "55") (name "Net-(U2-SW)") (class "Default")
      (node (ref "L2") (pin "1") (pinfunction "1_1") (pintype "passive"))
      (node (ref "U2") (pin "2") (pinfunction "SW_2") (pintype "bidirectional"))
    )
    (net (code "56") (name "Net-(U4-PA0{slash}XIN32{slash}EIC{slash}SCOM1PAD0{slash}TC2)") (class "Default")
      (node (ref "C46") (pin "2") (pinfunction "2_2") (pintype "passive"))
      (node (ref "U4") (pin "1") (pinfunction "PA0/XIN32/EIC/SCOM1PAD0/TC2_1") (pintype "bidirectional"))
      (node (ref "X1") (pin "1") (pinfunction "1_1") (pintype "passive"))
    )
    (net (code "57") (name "Net-(U4-PA1{slash}XOUT32{slash}EIC{slash}SCOM1PAD1{slash}TC2)") (class "Default")
      (node (ref "C45") (pin "2") (pinfunction "2_2") (pintype "passive"))
      (node (ref "U4") (pin "2") (pinfunction "PA1/XOUT32/EIC/SCOM1PAD1/TC2_2") (pintype "bidirectional"))
      (node (ref "X1") (pin "2") (pinfunction "2_2") (pintype "passive"))
    )
    (net (code "58") (name "Net-(U4-PA3{slash}EIC{slash}REF{slash}AIN1)") (class "Default")
      (node (ref "C19") (pin "2") (pinfunction "2_2") (pintype "passive"))
      (node (ref "U4") (pin "4") (pinfunction "PA3/EIC/REF/AIN1_4") (pintype "bidirectional"))
    )
    (net (code "59") (name "Net-(U5-ANT)") (class "Default")
      (node (ref "R25") (pin "1") (pinfunction "1_1") (pintype "passive"))
      (node (ref "R27") (pin "1") (pinfunction "1_1") (pintype "passive"))
      (node (ref "U5") (pin "40") (pinfunction "ANT_40") (pintype "bidirectional"))
    )
    (net (code "60") (name "Net-(U5-BT_ANT)") (class "Default")
      (node (ref "R23") (pin "2") (pinfunction "2_2") (pintype "passive"))
      (node (ref "R24") (pin "1") (pinfunction "1_1") (pintype "passive"))
      (node (ref "U5") (pin "36") (pinfunction "BT_ANT_36") (pintype "bidirectional"))
    )
    (net (code "61") (name "Net-(U5-FM_ANT_N)") (class "Default")
      (node (ref "TP6") (pin "T") (pinfunction "T_T") (pintype "bidirectional"))
      (node (ref "U5") (pin "57") (pinfunction "FM_ANT_N_57") (pintype "bidirectional"))
    )
    (net (code "62") (name "Net-(U5-FM_ANT_P)") (class "Default")
      (node (ref "TP7") (pin "T") (pinfunction "T_T") (pintype "bidirectional"))
      (node (ref "U5") (pin "17") (pinfunction "FM_ANT_P_17") (pintype "bidirectional"))
    )
    (net (code "63") (name "Net-(U5-NETLIGHT)") (class "Default")
      (node (ref "R29") (pin "1") (pinfunction "1_1") (pintype "passive"))
      (node (ref "U5") (pin "64") (pinfunction "NETLIGHT_64") (pintype "bidirectional"))
    )
    (net (code "64") (name "Net-(U5-RESET)") (class "Default")
      (node (ref "R21") (pin "1") (pinfunction "1_1") (pintype "passive"))
      (node (ref "U5") (pin "49") (pinfunction "RESET_49") (pintype "bidirectional"))
    )
    (net (code "65") (name "Net-(U5-STATUS)") (class "Default")
      (node (ref "R28") (pin "1") (pinfunction "1_1") (pintype "passive"))
      (node (ref "U5") (pin "4") (pinfunction "STATUS_4") (pintype "bidirectional"))
    )
    (net (code "66") (name "Net-(U5-VBUS)") (class "Default")
      (node (ref "TP8") (pin "T") (pinfunction "T_T") (pintype "bidirectional"))
      (node (ref "U5") (pin "7") (pinfunction "VBUS_7") (pintype "bidirectional"))
    )
    (net (code "67") (name "Net-(U5-VRTC)") (class "Default")
      (node (ref "C26") (pin "1") (pinfunction "1_1") (pintype "passive"))
      (node (ref "U5") (pin "56") (pinfunction "VRTC_56") (pintype "bidirectional"))
    )
    (net (code "68") (name "PA30_SWCLK") (class "Default")
      (node (ref "R17") (pin "2") (pinfunction "2_2") (pintype "passive"))
      (node (ref "U4") (pin "45") (pinfunction "PA30/EIC/SCOM1PAD2/TC1_45") (pintype "bidirectional"))
    )
    (net (code "69") (name "PA31_SWDIO") (class "Default")
      (node (ref "R16") (pin "2") (pinfunction "2_2") (pintype "passive"))
      (node (ref "U4") (pin "46") (pinfunction "PA31/EIC/SCOM1PAD3/TC1_46") (pintype "bidirectional"))
    )
    (net (code "70") (name "PB10_S4_SPI_MOSI") (class "Default")
      (node (ref "J3") (pin "8") (pinfunction "8_8") (pintype "bidirectional"))
      (node (ref "U4") (pin "19") (pinfunction "PB10/EIC/SCOM4PAD2/TC5_19") (pintype "bidirectional"))
    )
    (net (code "71") (name "PB11_S4_SPI_SCK") (class "Default")
      (node (ref "J3") (pin "4") (pinfunction "4_4") (pintype "bidirectional"))
      (node (ref "U4") (pin "20") (pinfunction "PB11/EIC/SCOM4PAD3/TC5_20") (pintype "bidirectional"))
    )
    (net (code "72") (name "PB12_S4_SPI_MISO") (class "Default")
      (node (ref "J3") (pin "7") (pinfunction "7_7") (pintype "bidirectional"))
      (node (ref "U4") (pin "21") (pinfunction "PA12/I2C/EIC/SCOM2PAD0+/TC2_21") (pintype "bidirectional"))
    )
    (net (code "73") (name "PB22_EDBG_TXD") (class "Default")
      (node (ref "J3") (pin "34") (pinfunction "34_34") (pintype "bidirectional"))
      (node (ref "U4") (pin "37") (pinfunction "PB22/EIC/SCOM5PAD2_37") (pintype "bidirectional"))
    )
    (net (code "74") (name "PB23_EDBG_RXD") (class "Default")
      (node (ref "J3") (pin "33") (pinfunction "33_33") (pintype "bidirectional"))
      (node (ref "U4") (pin "38") (pinfunction "PB23/EIC/SCOM5PAD3_38") (pintype "bidirectional"))
    )
    (net (code "75") (name "SCL") (class "Default")
      (node (ref "J3") (pin "30") (pinfunction "30_30") (pintype "bidirectional"))
      (node (ref "J4") (pin "3") (pinfunction "3_3") (pintype "bidirectional"))
      (node (ref "J4") (pin "9") (pinfunction "9_9") (pintype "bidirectional"))
      (node (ref "J6") (pin "2") (pinfunction "2_2") (pintype "bidirectional"))
      (node (ref "R13") (pin "1") (pinfunction "1_1") (pintype "passive"))
      (node (ref "U4") (pin "32") (pinfunction "PA23/I2C/EIC/SCOM5PAD1+/TC4_32") (pintype "bidirectional"))
    )
    (net (code "76") (name "SDA") (class "Default")
      (node (ref "J3") (pin "32") (pinfunction "32_32") (pintype "bidirectional"))
      (node (ref "J4") (pin "4") (pinfunction "4_4") (pintype "bidirectional"))
      (node (ref "J4") (pin "8") (pinfunction "8_8") (pintype "bidirectional"))
      (node (ref "J6") (pin "1") (pinfunction "1_1") (pintype "bidirectional"))
      (node (ref "R14") (pin "1") (pinfunction "1_1") (pintype "passive"))
      (node (ref "U4") (pin "31") (pinfunction "PA22/I2C/EIC/SCOM5PAD0+/TC4_31") (pintype "bidirectional"))
    )
    (net (code "77") (name "SIM_CLK") (class "Default")
      (node (ref "R37") (pin "1") (pinfunction "1_1") (pintype "passive"))
      (node (ref "U5") (pin "55") (pinfunction "SIM_CLK_55") (pintype "bidirectional"))
    )
    (net (code "78") (name "SIM_DATA") (class "Default")
      (node (ref "R38") (pin "2") (pinfunction "2_2") (pintype "passive"))
      (node (ref "U5") (pin "14") (pinfunction "SIM_DATA_14") (pintype "bidirectional"))
    )
    (net (code "79") (name "SIM_RST") (class "Default")
      (node (ref "R36") (pin "1") (pinfunction "1_1") (pintype "passive"))
      (node (ref "U5") (pin "15") (pinfunction "SIM_RST_15") (pintype "bidirectional"))
    )
    (net (code "80") (name "SIM_RXD") (class "Default")
      (node (ref "Q4") (pin "3") (pinfunction "D_3") (pintype "passive"))
      (node (ref "R35") (pin "2") (pinfunction "2_2") (pintype "passive"))
      (node (ref "U5") (pin "31") (pinfunction "UART1_RXD_31") (pintype "bidirectional"))
    )
    (net (code "81") (name "SIM_TXD") (class "Default")
      (node (ref "Q3") (pin "3") (pinfunction "D_3") (pintype "passive"))
      (node (ref "R33") (pin "2") (pinfunction "2_2") (pintype "passive"))
      (node (ref "U5") (pin "32") (pinfunction "UART1_TXD_32") (pintype "bidirectional"))
    )
    (net (code "82") (name "SPK_N") (class "Default")
      (node (ref "C34") (pin "1") (pinfunction "1_1") (pintype "passive"))
      (node (ref "C35") (pin "1") (pinfunction "1_1") (pintype "passive"))
      (node (ref "C44") (pin "1") (pinfunction "1_1") (pintype "passive"))
      (node (ref "J3") (pin "9") (pinfunction "9_9") (pintype "bidirectional"))
      (node (ref "U5") (pin "11") (pinfunction "SPK2N_11") (pintype "bidirectional"))
    )
    (net (code "83") (name "SPK_P") (class "Default")
      (node (ref "C33") (pin "1") (pinfunction "1_1") (pintype "passive"))
      (node (ref "C34") (pin "2") (pinfunction "2_2") (pintype "passive"))
      (node (ref "C43") (pin "1") (pinfunction "1_1") (pintype "passive"))
      (node (ref "J3") (pin "10") (pinfunction "10_10") (pintype "bidirectional"))
      (node (ref "U5") (pin "51") (pinfunction "SPK2P_51") (pintype "bidirectional"))
    )
    (net (code "84") (name "VCC_SIM") (class "Default")
      (node (ref "C10") (pin "2") (pinfunction "2_2") (pintype "passive"))
      (node (ref "C11") (pin "2") (pinfunction "2_2") (pintype "passive"))
      (node (ref "C12") (pin "2") (pinfunction "2_2") (pintype "passive"))
      (node (ref "C13") (pin "2") (pinfunction "2_2") (pintype "passive"))
      (node (ref "J3") (pin "27") (pinfunction "27_27") (pintype "bidirectional"))
      (node (ref "J3") (pin "28") (pinfunction "28_28") (pintype "bidirectional"))
      (node (ref "J4") (pin "10") (pinfunction "10_10") (pintype "bidirectional"))
      (node (ref "J4") (pin "2") (pinfunction "2_2") (pintype "bidirectional"))
      (node (ref "J6") (pin "3") (pinfunction "3_3") (pintype "bidirectional"))
      (node (ref "L2") (pin "2") (pinfunction "2_2") (pintype "passive"))
      (node (ref "R21") (pin "2") (pinfunction "2_2") (pintype "passive"))
      (node (ref "R33") (pin "1") (pinfunction "1_1") (pintype "passive"))
      (node (ref "R35") (pin "1") (pinfunction "1_1") (pintype "passive"))
      (node (ref "R9") (pin "2") (pinfunction "2_2") (pintype "passive"))
      (node (ref "U3") (pin "3") (pinfunction "VIN_3") (pintype "bidirectional"))
      (node (ref "U5") (pin "1") (pinfunction "VBAT_1") (pintype "bidirectional"))
      (node (ref "U5") (pin "42") (pinfunction "VBAT_42") (pintype "bidirectional"))
    )
    (net (code "85") (name "VSIM") (class "Default")
      (node (ref "C36") (pin "1") (pinfunction "1_1") (pintype "passive"))
      (node (ref "C37") (pin "1") (pinfunction "1_1") (pintype "passive"))
      (node (ref "SIM") (pin "1") (pinfunction "VCC_1") (pintype "bidirectional"))
      (node (ref "SIM") (pin "6") (pinfunction "VPP_6") (pintype "bidirectional"))
      (node (ref "U5") (pin "16") (pinfunction "VSIM_16") (pintype "bidirectional"))
    )
    (net (code "86") (name "VSYS") (class "Default")
      (node (ref "C3") (pin "1") (pinfunction "1_1") (pintype "passive"))
      (node (ref "C8") (pin "2") (pinfunction "2_2") (pintype "passive"))
      (node (ref "C9") (pin "2") (pinfunction "2_2") (pintype "passive"))
      (node (ref "D2") (pin "+") (pinfunction "+_+") (pintype "passive"))
      (node (ref "L1") (pin "2") (pinfunction "2_2") (pintype "passive"))
      (node (ref "TP2") (pin "T") (pinfunction "T_T") (pintype "bidirectional"))
      (node (ref "U1") (pin "1") (pinfunction "SYS_1") (pintype "bidirectional"))
      (node (ref "U1") (pin "15") (pinfunction "SYS_15") (pintype "bidirectional"))
      (node (ref "U2") (pin "5") (pinfunction "EN_5") (pintype "bidirectional"))
      (node (ref "U2") (pin "7") (pinfunction "AVIN_7") (pintype "bidirectional"))
      (node (ref "U2") (pin "8") (pinfunction "PVIN_8") (pintype "bidirectional"))
    )
    (net (code "87") (name "VUSB") (class "Default")
      (node (ref "C1") (pin "1") (pinfunction "1_1") (pintype "passive"))
      (node (ref "C2") (pin "1") (pinfunction "1_1") (pintype "passive"))
      (node (ref "C7") (pin "1") (pinfunction "1_1") (pintype "passive"))
      (node (ref "J1") (pin "1") (pinfunction "VCC_1") (pintype "bidirectional"))
      (node (ref "R1") (pin "1") (pinfunction "1_1") (pintype "passive"))
      (node (ref "R6") (pin "2") (pinfunction "2_2") (pintype "passive"))
      (node (ref "TP1") (pin "T") (pinfunction "T_T") (pintype "bidirectional"))
      (node (ref "U1") (pin "2") (pinfunction "IN_2") (pintype "bidirectional"))
    )
    (net (code "88") (name "unconnected-(J1-ID-Pad4)") (class "Default")
      (node (ref "J1") (pin "4") (pinfunction "ID_4") (pintype "bidirectional"))
    )
    (net (code "89") (name "unconnected-(TP4-PadT)") (class "Default")
      (node (ref "TP4") (pin "T") (pinfunction "T_T") (pintype "bidirectional"))
    )
    (net (code "90") (name "unconnected-(TP5-PadT)") (class "Default")
      (node (ref "TP5") (pin "T") (pinfunction "T_T") (pintype "bidirectional"))
    )
    (net (code "91") (name "unconnected-(U4-PA13{slash}I2C{slash}EIC{slash}SCOM2PAD1+{slash}TC2-Pad22)") (class "Default")
      (node (ref "U4") (pin "22") (pinfunction "PA13/I2C/EIC/SCOM2PAD1+/TC2_22") (pintype "bidirectional"))
    )
    (net (code "92") (name "unconnected-(U4-PA27{slash}EIC-Pad39)") (class "Default")
      (node (ref "U4") (pin "39") (pinfunction "PA27/EIC_39") (pintype "bidirectional"))
    )
    (net (code "93") (name "unconnected-(U4-PA28{slash}EIC-Pad41)") (class "Default")
      (node (ref "U4") (pin "41") (pinfunction "PA28/EIC_41") (pintype "bidirectional"))
    )
    (net (code "94") (name "unconnected-(U4-PB3{slash}EIC{slash}AIN11{slash}SCOM5PAD1-Pad48)") (class "Default")
      (node (ref "U4") (pin "48") (pinfunction "PB3/EIC/AIN11/SCOM5PAD1_48") (pintype "bidirectional"))
    )
    (net (code "95") (name "unconnected-(U5-ADC-Pad50)") (class "Default")
      (node (ref "U5") (pin "50") (pinfunction "ADC_50") (pintype "bidirectional"))
    )
    (net (code "96") (name "unconnected-(U5-BPI_BUS1-Pad5)") (class "Default")
      (node (ref "U5") (pin "5") (pinfunction "BPI_BUS1_5") (pintype "bidirectional"))
    )
    (net (code "97") (name "unconnected-(U5-COL0-Pad20)") (class "Default")
      (node (ref "U5") (pin "20") (pinfunction "COL0_20") (pintype "bidirectional"))
    )
    (net (code "98") (name "unconnected-(U5-COL1-Pad25)") (class "Default")
      (node (ref "U5") (pin "25") (pinfunction "COL1_25") (pintype "bidirectional"))
    )
    (net (code "99") (name "unconnected-(U5-COL2-Pad22)") (class "Default")
      (node (ref "U5") (pin "22") (pinfunction "COL2_22") (pintype "bidirectional"))
    )
    (net (code "100") (name "unconnected-(U5-COL3-Pad21)") (class "Default")
      (node (ref "U5") (pin "21") (pinfunction "COL3_21") (pintype "bidirectional"))
    )
    (net (code "101") (name "unconnected-(U5-COL4-Pad24)") (class "Default")
      (node (ref "U5") (pin "24") (pinfunction "COL4_24") (pintype "bidirectional"))
    )
    (net (code "102") (name "unconnected-(U5-GPIO1-Pad3)") (class "Default")
      (node (ref "U5") (pin "3") (pinfunction "GPIO1_3") (pintype "bidirectional"))
    )
    (net (code "103") (name "unconnected-(U5-GPIO2-Pad27)") (class "Default")
      (node (ref "U5") (pin "27") (pinfunction "GPIO2_27") (pintype "bidirectional"))
    )
    (net (code "104") (name "unconnected-(U5-GPIO3-Pad28)") (class "Default")
      (node (ref "U5") (pin "28") (pinfunction "GPIO3_28") (pintype "bidirectional"))
    )
    (net (code "105") (name "unconnected-(U5-ISINK0-Pad47)") (class "Default")
      (node (ref "U5") (pin "47") (pinfunction "ISINK0_47") (pintype "bidirectional"))
    )
    (net (code "106") (name "unconnected-(U5-ISINK1-Pad46)") (class "Default")
      (node (ref "U5") (pin "46") (pinfunction "ISINK1_46") (pintype "bidirectional"))
    )
    (net (code "107") (name "unconnected-(U5-PCMCLK-Pad29)") (class "Default")
      (node (ref "U5") (pin "29") (pinfunction "PCMCLK_29") (pintype "bidirectional"))
    )
    (net (code "108") (name "unconnected-(U5-PCMIN-Pad66)") (class "Default")
      (node (ref "U5") (pin "66") (pinfunction "PCMIN_66") (pintype "bidirectional"))
    )
    (net (code "109") (name "unconnected-(U5-PCMOUT-Pad30)") (class "Default")
      (node (ref "U5") (pin "30") (pinfunction "PCMOUT_30") (pintype "bidirectional"))
    )
    (net (code "110") (name "unconnected-(U5-PCMSYNC-Pad65)") (class "Default")
      (node (ref "U5") (pin "65") (pinfunction "PCMSYNC_65") (pintype "bidirectional"))
    )
    (net (code "111") (name "unconnected-(U5-PWM-Pad26)") (class "Default")
      (node (ref "U5") (pin "26") (pinfunction "PWM_26") (pintype "bidirectional"))
    )
    (net (code "112") (name "unconnected-(U5-ROW0-Pad62)") (class "Default")
      (node (ref "U5") (pin "62") (pinfunction "ROW0_62") (pintype "bidirectional"))
    )
    (net (code "113") (name "unconnected-(U5-ROW1-Pad60)") (class "Default")
      (node (ref "U5") (pin "60") (pinfunction "ROW1_60") (pintype "bidirectional"))
    )
    (net (code "114") (name "unconnected-(U5-ROW2-Pad61)") (class "Default")
      (node (ref "U5") (pin "61") (pinfunction "ROW2_61") (pintype "bidirectional"))
    )
    (net (code "115") (name "unconnected-(U5-ROW3-Pad23)") (class "Default")
      (node (ref "U5") (pin "23") (pinfunction "ROW3_23") (pintype "bidirectional"))
    )
    (net (code "116") (name "unconnected-(U5-ROW4-Pad63)") (class "Default")
      (node (ref "U5") (pin "63") (pinfunction "ROW4_63") (pintype "bidirectional"))
    )
    (net (code "117") (name "unconnected-(U5-SCL-Pad74)") (class "Default")
      (node (ref "U5") (pin "74") (pinfunction "SCL_74") (pintype "bidirectional"))
    )
    (net (code "118") (name "unconnected-(U5-SDA-Pad75)") (class "Default")
      (node (ref "U5") (pin "75") (pinfunction "SDA_75") (pintype "bidirectional"))
    )
    (net (code "119") (name "unconnected-(U5-SIMPRE-Pad54)") (class "Default")
      (node (ref "U5") (pin "54") (pinfunction "SIMPRE_54") (pintype "bidirectional"))
    )
    (net (code "120") (name "unconnected-(U5-UART1_CTS-Pad34)") (class "Default")
      (node (ref "U5") (pin "34") (pinfunction "UART1_CTS_34") (pintype "bidirectional"))
    )
    (net (code "121") (name "unconnected-(U5-UART1_DCD-Pad70)") (class "Default")
      (node (ref "U5") (pin "70") (pinfunction "UART1_DCD_70") (pintype "bidirectional"))
    )
    (net (code "122") (name "unconnected-(U5-UART1_DTR-Pad69)") (class "Default")
      (node (ref "U5") (pin "69") (pinfunction "UART1_DTR_69") (pintype "bidirectional"))
    )
    (net (code "123") (name "unconnected-(U5-UART1_RI-Pad68)") (class "Default")
      (node (ref "U5") (pin "68") (pinfunction "UART1_RI_68") (pintype "bidirectional"))
    )
    (net (code "124") (name "unconnected-(U5-UART1_RTS-Pad33)") (class "Default")
      (node (ref "U5") (pin "33") (pinfunction "UART1_RTS_33") (pintype "bidirectional"))
    )
    (net (code "125") (name "unconnected-(U5-USB_DM-Pad19)") (class "Default")
      (node (ref "U5") (pin "19") (pinfunction "USB_DM_19") (pintype "bidirectional"))
    )
    (net (code "126") (name "unconnected-(U5-USB_DP-Pad59)") (class "Default")
      (node (ref "U5") (pin "59") (pinfunction "USB_DP_59") (pintype "bidirectional"))
    )
    (net (code "127") (name "unconnected-(U5-VEXT-Pad18)") (class "Default")
      (node (ref "U5") (pin "18") (pinfunction "VEXT_18") (pintype "bidirectional"))
    )
  )
)
